# Input_Mode_Selector.net
KiCad netlist of a schematic drawn in Altium Designer
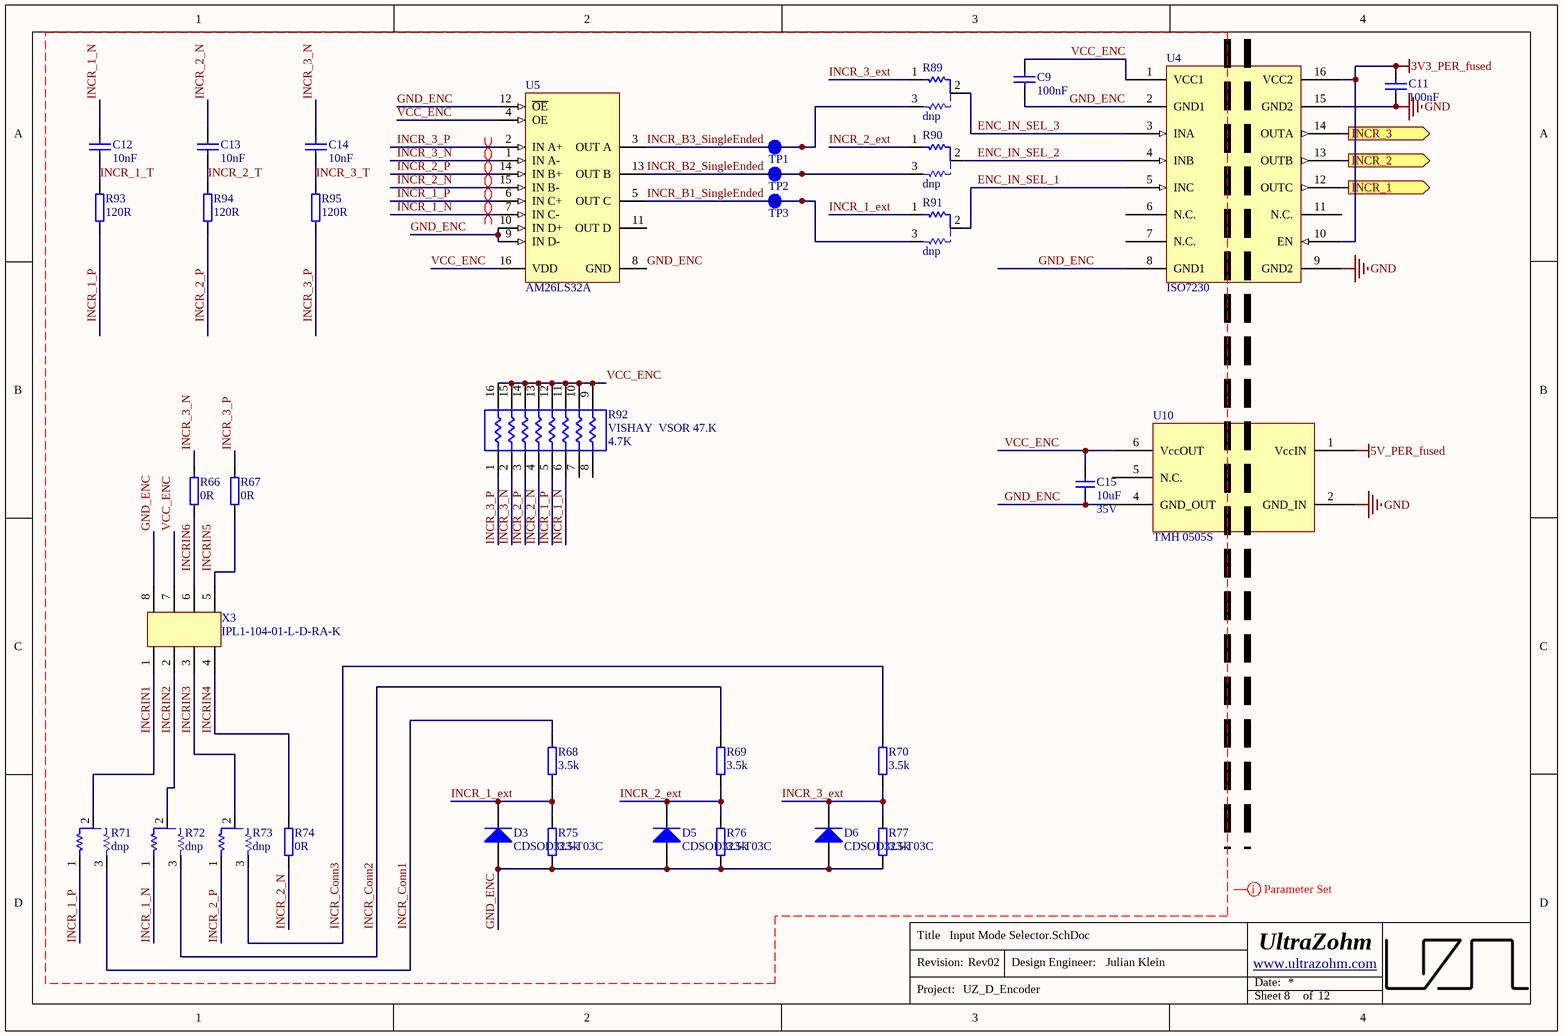
[diagram p0: Input Mode Selector.SchDoc]

(export (version "E")
  (design (tool "Eeschema 10.0.6"))
  (components
    (comp (ref "C9")
      (value "100nF")
      (footprint "CAPC1608X07N")
      (fields (field (name "MF") "Würth") (field (name "MPN") "885012206071") (field (name "VOLTAGE") "25V"))
      (libsource (lib "UltraZohm_ADC") (part "Cap_0603"))
    )
    (comp (ref "C11")
      (value "100nF")
      (footprint "CAPC1608X07N")
      (fields (field (name "MF") "Würth") (field (name "MPN") "885012206071") (field (name "VOLTAGE") "25V"))
      (libsource (lib "UltraZohm_ADC") (part "Cap_0603"))
    )
    (comp (ref "C12")
      (value "10nF")
      (footprint "CAPC1608X07N")
      (fields (field (name "MF") "Würth") (field (name "MPN") "885012206065") (field (name "VOLTAGE") "25V"))
      (libsource (lib "UltraZohm_ADC") (part "Cap_0603"))
    )
    (comp (ref "C13")
      (value "10nF")
      (footprint "CAPC1608X07N")
      (fields (field (name "MF") "Würth") (field (name "MPN") "885012206065") (field (name "VOLTAGE") "25V"))
      (libsource (lib "UltraZohm_ADC") (part "Cap_0603"))
    )
    (comp (ref "C14")
      (value "10nF")
      (footprint "CAPC1608X07N")
      (fields (field (name "MF") "Würth") (field (name "MPN") "885012206065") (field (name "VOLTAGE") "25V"))
      (libsource (lib "UltraZohm_ADC") (part "Cap_0603"))
    )
    (comp (ref "C15")
      (value "10uF")
      (footprint "C_1206")
      (description "Capacitor 1206")
      (fields
        (field (name "TOLERANCE") "10%")
        (field (name "MF") "Murata Electronics")
        (field (name "VOLTAGE") "35V")
        (field (name "CREATED") "2018_06_25_AGeiger")
      )
      (libsource (lib "UltraZohm_ADC") (part "C_1206"))
    )
    (comp (ref "D3")
      (value "CDSOD323-T03C")
      (footprint "SOD-323")
      (description "TVS DIODE 3.3V 19V SOD323")
      (fields (field (name "MF") "Bourns"))
      (libsource (lib "Componentes_SOC") (part "Diodo TVS"))
    )
    (comp (ref "D5")
      (value "CDSOD323-T03C")
      (footprint "SOD-323")
      (description "TVS DIODE 3.3V 19V SOD323")
      (fields (field (name "MF") "Bourns"))
      (libsource (lib "Componentes_SOC") (part "Diodo TVS"))
    )
    (comp (ref "D6")
      (value "CDSOD323-T03C")
      (footprint "SOD-323")
      (description "TVS DIODE 3.3V 19V SOD323")
      (fields (field (name "MF") "Bourns"))
      (libsource (lib "Componentes_SOC") (part "Diodo TVS"))
    )
    (comp (ref "R66")
      (value "0R")
      (footprint "RESC1608X06N")
      (fields (field (name "MF") "Vishay") (field (name "MPN") "CRCW06030000Z0EAC"))
      (libsource (lib "UltraZohm_ADC") (part "R_0603"))
    )
    (comp (ref "R67")
      (value "0R")
      (footprint "RESC1608X06N")
      (fields (field (name "MF") "Vishay") (field (name "MPN") "CRCW06030000Z0EAC"))
      (libsource (lib "UltraZohm_ADC") (part "R_0603"))
    )
    (comp (ref "R68")
      (value "3.5k")
      (footprint "RESC1608X06N")
      (libsource (lib "UltraZohm_ADC") (part "R_0603"))
    )
    (comp (ref "R69")
      (value "3.5k")
      (footprint "RESC1608X06N")
      (libsource (lib "UltraZohm_ADC") (part "R_0603"))
    )
    (comp (ref "R70")
      (value "3.5k")
      (footprint "RESC1608X06N")
      (libsource (lib "UltraZohm_ADC") (part "R_0603"))
    )
    (comp (ref "R71")
      (value "dnp")
      (footprint "0603_Config")
      (fields
        (field (name "MPN") "MCWR06X1002FTL")
        (field (name "MF") "Multicomp")
        (field (name "VOLTAGE") "50V")
        (field (name "CREATED") "2018_09_04_AGeiger")
      )
      (libsource (lib "Componentes_SOC") (part "R_config"))
    )
    (comp (ref "R72")
      (value "dnp")
      (footprint "0603_Config")
      (fields
        (field (name "MPN") "MCWR06X1002FTL")
        (field (name "MF") "Multicomp")
        (field (name "VOLTAGE") "50V")
        (field (name "CREATED") "2018_09_04_AGeiger")
      )
      (libsource (lib "Componentes_SOC") (part "R_config"))
    )
    (comp (ref "R73")
      (value "dnp")
      (footprint "0603_Config")
      (fields
        (field (name "MPN") "MCWR06X1002FTL")
        (field (name "MF") "Multicomp")
        (field (name "VOLTAGE") "50V")
        (field (name "CREATED") "2018_09_04_AGeiger")
      )
      (libsource (lib "Componentes_SOC") (part "R_config"))
    )
    (comp (ref "R74")
      (value "0R")
      (footprint "RESC1608X06N")
      (fields (field (name "MF") "Vishay") (field (name "MPN") "CRCW06030000Z0EAC"))
      (libsource (lib "UltraZohm_ADC") (part "R_0603"))
    )
    (comp (ref "R75")
      (value "3.5k")
      (footprint "RESC1608X06N")
      (libsource (lib "UltraZohm_ADC") (part "R_0603"))
    )
    (comp (ref "R76")
      (value "3.5k")
      (footprint "RESC1608X06N")
      (libsource (lib "UltraZohm_ADC") (part "R_0603"))
    )
    (comp (ref "R77")
      (value "3.5k")
      (footprint "RESC1608X06N")
      (libsource (lib "UltraZohm_ADC") (part "R_0603"))
    )
    (comp (ref "R89")
      (value "dnp")
      (footprint "0603_Config")
      (fields
        (field (name "MPN") "MCWR06X1002FTL")
        (field (name "MF") "Multicomp")
        (field (name "VOLTAGE") "50V")
        (field (name "CREATED") "2018_09_04_AGeiger")
      )
      (libsource (lib "Componentes_SOC") (part "R_config"))
    )
    (comp (ref "R90")
      (value "dnp")
      (footprint "0603_Config")
      (fields
        (field (name "MPN") "MCWR06X1002FTL")
        (field (name "MF") "Multicomp")
        (field (name "VOLTAGE") "50V")
        (field (name "CREATED") "2018_09_04_AGeiger")
      )
      (libsource (lib "Componentes_SOC") (part "R_config"))
    )
    (comp (ref "R91")
      (value "dnp")
      (footprint "0603_Config")
      (fields
        (field (name "MPN") "MCWR06X1002FTL")
        (field (name "MF") "Multicomp")
        (field (name "VOLTAGE") "50V")
        (field (name "CREATED") "2018_09_04_AGeiger")
      )
      (libsource (lib "Componentes_SOC") (part "R_config"))
    )
    (comp (ref "R92")
      (value "VISHAY  VSOR 47.K")
      (footprint "SO-16_N")
      (description "Isolated Resistor Network")
      (fields (field (name "ALTIUM_VALUE") "4.7K") (field (name "PUBLISHER") "Altium Limited"))
      (libsource (lib "Miscellaneous Devices") (part "Res Pack3"))
    )
    (comp (ref "R93")
      (value "120R")
      (footprint "RESC1608X06N")
      (libsource (lib "UltraZohm_ADC") (part "R_0603"))
    )
    (comp (ref "R94")
      (value "120R")
      (footprint "RESC1608X06N")
      (libsource (lib "UltraZohm_ADC") (part "R_0603"))
    )
    (comp (ref "R95")
      (value "120R")
      (footprint "RESC1608X06N")
      (libsource (lib "UltraZohm_ADC") (part "R_0603"))
    )
    (comp (ref "TP1")
      (value "VCC")
      (footprint "TP_1mm")
      (description "Testpoint 1mm")
      (fields (field (name "CREATED") "2018_06_25_AGeiger"))
      (libsource (lib "UltraZOhm_CarrierBoard") (part "TP_1mm"))
    )
    (comp (ref "TP2")
      (value "VCC")
      (footprint "TP_1mm")
      (description "Testpoint 1mm")
      (fields (field (name "CREATED") "2018_06_25_AGeiger"))
      (libsource (lib "UltraZOhm_CarrierBoard") (part "TP_1mm"))
    )
    (comp (ref "TP3")
      (value "VCC")
      (footprint "TP_1mm")
      (description "Testpoint 1mm")
      (fields (field (name "CREATED") "2018_06_25_AGeiger"))
      (libsource (lib "UltraZOhm_CarrierBoard") (part "TP_1mm"))
    )
    (comp (ref "U4")
      (value "ISO7230")
      (footprint "SOIC-16_wide-body")
      (description "High-Speed, Triple-Channel Digital Isolator")
      (libsource (lib "MezzaninBoard") (part "TI ISO7230"))
    )
    (comp (ref "U5")
      (value "AM26LS32A")
      (footprint "M16A_N")
      (description "Quad Differential Line Receiver, 16-pin Narrow SOIC")
      (fields (field (name "PARTNUMBER") "AM26LS32AIDR") (field (name "MANUFACTURER") "TI"))
      (libsource (lib "NSC Interface") (part "DS26LS32CM"))
    )
    (comp (ref "U10")
      (value "TMH 0505S")
      (footprint "SIL-6(7)")
      (description "5V/5V DC-DC Isolation Converter")
      (libsource (lib "MezzaninBoard") (part "TRACO TMH 0505S"))
    )
    (comp (ref "X3")
      (value "IPL1-104-01-L-D-RA-K")
      (footprint "Conector 4x2 TH Horizontal")
      (description "CONN HEADER R/A 8POS 2.54MM Through Hole")
      (fields (field (name "MF") "Samtec"))
      (libsource (lib "Componentes_SOC") (part "Conector 4x2 Horizontal"))
    )
  )
  (nets
    (net (code "1") (name "/ENC_IN_SEL_1") (class "Default")
      (node (ref "R91") (pin "2") (pinfunction "2_2") (pintype "passive"))
      (node (ref "U4") (pin "5") (pinfunction "INC_5") (pintype "input"))
    )
    (net (code "2") (name "/ENC_IN_SEL_2") (class "Default")
      (node (ref "R90") (pin "2") (pinfunction "2_2") (pintype "passive"))
      (node (ref "U4") (pin "4") (pinfunction "INB_4") (pintype "input"))
    )
    (net (code "3") (name "/ENC_IN_SEL_3") (class "Default")
      (node (ref "R89") (pin "2") (pinfunction "2_2") (pintype "passive"))
      (node (ref "U4") (pin "3") (pinfunction "INA_3") (pintype "input"))
    )
    (net (code "4") (name "/GND_ENC") (class "Default")
      (node (ref "C15") (pin "1") (pinfunction "1_1") (pintype "passive"))
      (node (ref "C9") (pin "1") (pinfunction "1_1") (pintype "passive"))
      (node (ref "D3") (pin "2") (pinfunction "A_2") (pintype "passive"))
      (node (ref "D5") (pin "2") (pinfunction "A_2") (pintype "passive"))
      (node (ref "D6") (pin "2") (pinfunction "A_2") (pintype "passive"))
      (node (ref "R75") (pin "2") (pintype "passive"))
      (node (ref "R76") (pin "2") (pintype "passive"))
      (node (ref "R77") (pin "2") (pintype "passive"))
      (node (ref "U10") (pin "4") (pinfunction "GND_OUT_4") (pintype "passive"))
      (node (ref "U4") (pin "2") (pinfunction "GND1_2") (pintype "passive"))
      (node (ref "U4") (pin "8") (pinfunction "GND1_8") (pintype "passive"))
      (node (ref "U5") (pin "10") (pinfunction "IN_D+_10") (pintype "input"))
      (node (ref "U5") (pin "12") (pinfunction "~{OE}_12") (pintype "input"))
      (node (ref "U5") (pin "8") (pinfunction "GND_8") (pintype "power_in"))
      (node (ref "U5") (pin "9") (pinfunction "IN_D-_9") (pintype "input"))
      (node (ref "X3") (pin "8") (pintype "passive"))
    )
    (net (code "5") (name "/INCRIN1") (class "Default")
      (node (ref "R71") (pin "2") (pinfunction "2_2") (pintype "passive"))
      (node (ref "X3") (pin "1") (pintype "passive"))
    )
    (net (code "6") (name "/INCRIN2") (class "Default")
      (node (ref "R72") (pin "2") (pinfunction "2_2") (pintype "passive"))
      (node (ref "X3") (pin "2") (pintype "passive"))
    )
    (net (code "7") (name "/INCRIN3") (class "Default")
      (node (ref "R73") (pin "2") (pinfunction "2_2") (pintype "passive"))
      (node (ref "X3") (pin "3") (pintype "passive"))
    )
    (net (code "8") (name "/INCRIN4") (class "Default")
      (node (ref "R74") (pin "2") (pintype "passive"))
      (node (ref "X3") (pin "4") (pintype "passive"))
    )
    (net (code "9") (name "/INCRIN5") (class "Default")
      (node (ref "R67") (pin "1") (pintype "passive"))
      (node (ref "X3") (pin "5") (pintype "passive"))
    )
    (net (code "10") (name "/INCRIN6") (class "Default")
      (node (ref "R66") (pin "1") (pintype "passive"))
      (node (ref "X3") (pin "6") (pintype "passive"))
    )
    (net (code "11") (name "/INCR_1") (class "Default")
      (node (ref "U4") (pin "12") (pinfunction "OUTC_12") (pintype "output"))
    )
    (net (code "12") (name "/INCR_1_N") (class "Default")
      (node (ref "C12") (pin "2") (pinfunction "2_2") (pintype "passive"))
      (node (ref "R72") (pin "1") (pinfunction "1_1") (pintype "passive"))
      (node (ref "R92") (pin "6") (pinfunction "6_6") (pintype "passive"))
      (node (ref "U5") (pin "7") (pinfunction "IN_C-_7") (pintype "input"))
    )
    (net (code "13") (name "/INCR_1_P") (class "Default")
      (node (ref "R71") (pin "1") (pinfunction "1_1") (pintype "passive"))
      (node (ref "R92") (pin "5") (pinfunction "5_5") (pintype "passive"))
      (node (ref "R93") (pin "1") (pintype "passive"))
      (node (ref "U5") (pin "6") (pinfunction "IN_C+_6") (pintype "input"))
    )
    (net (code "14") (name "/INCR_1_T") (class "Default")
      (node (ref "C12") (pin "1") (pinfunction "1_1") (pintype "passive"))
      (node (ref "R93") (pin "2") (pintype "passive"))
    )
    (net (code "15") (name "/INCR_1_ext") (class "Default")
      (node (ref "D3") (pin "1") (pinfunction "K_1") (pintype "passive"))
      (node (ref "R68") (pin "2") (pintype "passive"))
      (node (ref "R75") (pin "1") (pintype "passive"))
      (node (ref "R91") (pin "1") (pinfunction "1_1") (pintype "passive"))
    )
    (net (code "16") (name "/INCR_2") (class "Default")
      (node (ref "U4") (pin "13") (pinfunction "OUTB_13") (pintype "output"))
    )
    (net (code "17") (name "/INCR_2_N") (class "Default")
      (node (ref "C13") (pin "2") (pinfunction "2_2") (pintype "passive"))
      (node (ref "R74") (pin "1") (pintype "passive"))
      (node (ref "R92") (pin "4") (pinfunction "4_4") (pintype "passive"))
      (node (ref "U5") (pin "15") (pinfunction "IN_B-_15") (pintype "input"))
    )
    (net (code "18") (name "/INCR_2_P") (class "Default")
      (node (ref "R73") (pin "1") (pinfunction "1_1") (pintype "passive"))
      (node (ref "R92") (pin "3") (pinfunction "3_3") (pintype "passive"))
      (node (ref "R94") (pin "1") (pintype "passive"))
      (node (ref "U5") (pin "14") (pinfunction "IN_B+_14") (pintype "input"))
    )
    (net (code "19") (name "/INCR_2_T") (class "Default")
      (node (ref "C13") (pin "1") (pinfunction "1_1") (pintype "passive"))
      (node (ref "R94") (pin "2") (pintype "passive"))
    )
    (net (code "20") (name "/INCR_2_ext") (class "Default")
      (node (ref "D5") (pin "1") (pinfunction "K_1") (pintype "passive"))
      (node (ref "R69") (pin "2") (pintype "passive"))
      (node (ref "R76") (pin "1") (pintype "passive"))
      (node (ref "R90") (pin "1") (pinfunction "1_1") (pintype "passive"))
    )
    (net (code "21") (name "/INCR_3") (class "Default")
      (node (ref "U4") (pin "14") (pinfunction "OUTA_14") (pintype "output"))
    )
    (net (code "22") (name "/INCR_3_N") (class "Default")
      (node (ref "C14") (pin "2") (pinfunction "2_2") (pintype "passive"))
      (node (ref "R66") (pin "2") (pintype "passive"))
      (node (ref "R92") (pin "2") (pinfunction "2_2") (pintype "passive"))
      (node (ref "U5") (pin "1") (pinfunction "IN_A-_1") (pintype "input"))
    )
    (net (code "23") (name "/INCR_3_P") (class "Default")
      (node (ref "R67") (pin "2") (pintype "passive"))
      (node (ref "R92") (pin "1") (pinfunction "1_1") (pintype "passive"))
      (node (ref "R95") (pin "1") (pintype "passive"))
      (node (ref "U5") (pin "2") (pinfunction "IN_A+_2") (pintype "input"))
    )
    (net (code "24") (name "/INCR_3_T") (class "Default")
      (node (ref "C14") (pin "1") (pinfunction "1_1") (pintype "passive"))
      (node (ref "R95") (pin "2") (pintype "passive"))
    )
    (net (code "25") (name "/INCR_3_ext") (class "Default")
      (node (ref "D6") (pin "1") (pinfunction "K_1") (pintype "passive"))
      (node (ref "R70") (pin "2") (pintype "passive"))
      (node (ref "R77") (pin "1") (pintype "passive"))
      (node (ref "R89") (pin "1") (pinfunction "1_1") (pintype "passive"))
    )
    (net (code "26") (name "/INCR_B1_SingleEnded") (class "Default")
      (node (ref "R91") (pin "3") (pinfunction "3_3") (pintype "passive"))
      (node (ref "TP3") (pin "1") (pintype "passive"))
      (node (ref "U5") (pin "5") (pinfunction "OUT_C_5") (pintype "tri_state"))
    )
    (net (code "27") (name "/INCR_B2_SingleEnded") (class "Default")
      (node (ref "R90") (pin "3") (pinfunction "3_3") (pintype "passive"))
      (node (ref "TP2") (pin "1") (pintype "passive"))
      (node (ref "U5") (pin "13") (pinfunction "OUT_B_13") (pintype "tri_state"))
    )
    (net (code "28") (name "/INCR_B3_SingleEnded") (class "Default")
      (node (ref "R89") (pin "3") (pinfunction "3_3") (pintype "passive"))
      (node (ref "TP1") (pin "1") (pintype "passive"))
      (node (ref "U5") (pin "3") (pinfunction "OUT_A_3") (pintype "tri_state"))
    )
    (net (code "29") (name "/INCR_Conn1") (class "Default")
      (node (ref "R68") (pin "1") (pintype "passive"))
      (node (ref "R71") (pin "3") (pinfunction "3_3") (pintype "passive"))
    )
    (net (code "30") (name "/INCR_Conn2") (class "Default")
      (node (ref "R69") (pin "1") (pintype "passive"))
      (node (ref "R72") (pin "3") (pinfunction "3_3") (pintype "passive"))
    )
    (net (code "31") (name "/INCR_Conn3") (class "Default")
      (node (ref "R70") (pin "1") (pintype "passive"))
      (node (ref "R73") (pin "3") (pinfunction "3_3") (pintype "passive"))
    )
    (net (code "32") (name "/VCC_ENC") (class "Default")
      (node (ref "C15") (pin "2") (pinfunction "2_2") (pintype "passive"))
      (node (ref "C9") (pin "2") (pinfunction "2_2") (pintype "passive"))
      (node (ref "R92") (pin "10") (pinfunction "10_10") (pintype "passive"))
      (node (ref "R92") (pin "11") (pinfunction "11_11") (pintype "passive"))
      (node (ref "R92") (pin "12") (pinfunction "12_12") (pintype "passive"))
      (node (ref "R92") (pin "13") (pinfunction "13_13") (pintype "passive"))
      (node (ref "R92") (pin "14") (pinfunction "14_14") (pintype "passive"))
      (node (ref "R92") (pin "15") (pinfunction "15_15") (pintype "passive"))
      (node (ref "R92") (pin "16") (pinfunction "16_16") (pintype "passive"))
      (node (ref "R92") (pin "9") (pinfunction "9_9") (pintype "passive"))
      (node (ref "U10") (pin "6") (pinfunction "VccOUT_6") (pintype "passive"))
      (node (ref "U4") (pin "1") (pinfunction "VCC1_1") (pintype "passive"))
      (node (ref "U5") (pin "16") (pinfunction "VDD_16") (pintype "power_in"))
      (node (ref "U5") (pin "4") (pinfunction "OE_4") (pintype "input"))
      (node (ref "X3") (pin "7") (pintype "passive"))
    )
    (net (code "33") (name "3V3_PER_fused") (class "Default")
      (node (ref "C11") (pin "2") (pinfunction "2_2") (pintype "passive"))
      (node (ref "U4") (pin "10") (pinfunction "EN_10") (pintype "input"))
      (node (ref "U4") (pin "16") (pinfunction "VCC2_16") (pintype "passive"))
    )
    (net (code "34") (name "5V_PER_fused") (class "Default")
      (node (ref "U10") (pin "1") (pinfunction "VccIN_1") (pintype "passive"))
    )
    (net (code "35") (name "GND") (class "Default")
      (node (ref "C11") (pin "1") (pinfunction "1_1") (pintype "passive"))
      (node (ref "U10") (pin "2") (pinfunction "GND_IN_2") (pintype "passive"))
      (node (ref "U4") (pin "15") (pinfunction "GND2_15") (pintype "passive"))
      (node (ref "U4") (pin "9") (pinfunction "GND2_9") (pintype "passive"))
    )
    (net (code "36") (name "unconnected-(R92-Pad7)") (class "Default")
      (node (ref "R92") (pin "7") (pinfunction "7_7") (pintype "passive"))
    )
    (net (code "37") (name "unconnected-(R92-Pad8)") (class "Default")
      (node (ref "R92") (pin "8") (pinfunction "8_8") (pintype "passive"))
    )
    (net (code "38") (name "unconnected-(U4-N.C.-Pad6)") (class "Default")
      (node (ref "U4") (pin "6") (pinfunction "N.C._6") (pintype "passive"))
    )
    (net (code "39") (name "unconnected-(U4-N.C.-Pad7)") (class "Default")
      (node (ref "U4") (pin "7") (pinfunction "N.C._7") (pintype "passive"))
    )
    (net (code "40") (name "unconnected-(U4-N.C.-Pad11)") (class "Default")
      (node (ref "U4") (pin "11") (pinfunction "N.C._11") (pintype "passive"))
    )
    (net (code "41") (name "unconnected-(U5-OUT_D-Pad11)") (class "Default")
      (node (ref "U5") (pin "11") (pinfunction "OUT_D_11") (pintype "tri_state"))
    )
    (net (code "42") (name "unconnected-(U10-N.C.-Pad5)") (class "Default")
      (node (ref "U10") (pin "5") (pinfunction "N.C._5") (pintype "passive"))
    )
  )
)
